# as5047_breakout.net
KiCad netlist of a schematic drawn in EAGLE
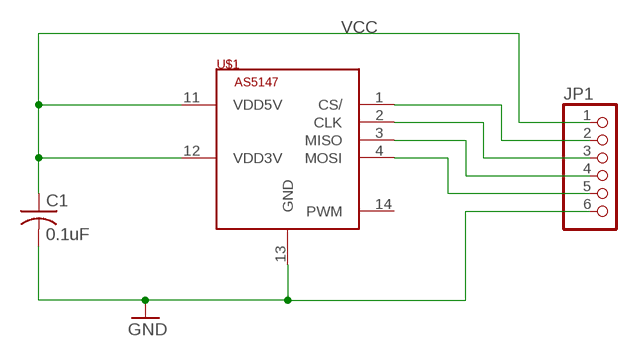
[diagram p0: schematic, sheet 1]

(export (version "E")
  (design (tool "Eeschema 10.0.6"))
  (components
    (comp (ref "C1")
      (value "0.1uF")
      (footprint "eagle-import:C0603")
      (libsource (lib "eagle-import") (part "C-USC0603"))
    )
    (comp (ref "JP1")
      (value "PINHD-1X6")
      (footprint "eagle-import:1X06")
      (libsource (lib "eagle-import") (part "PINHD-1X6"))
    )
    (comp (ref "U$1")
      (value "AS5147")
      (footprint "eagle-import:TSSOP14")
      (fields (field (name "MFG") "AMS") (field (name "MPN") "AS5047D-ATSM"))
      (libsource (lib "eagle-import") (part "AS5147"))
    )
  )
  (nets
    (net (code "1") (name "/VCC") (class "Default")
      (node (ref "C1") (pin "1") (pinfunction "1_1") (pintype "passive"))
      (node (ref "JP1") (pin "1") (pinfunction "1_1") (pintype "passive"))
      (node (ref "U$1") (pin "11") (pinfunction "VDD5V_11") (pintype "bidirectional"))
      (node (ref "U$1") (pin "12") (pinfunction "VDD3V_12") (pintype "bidirectional"))
    )
    (net (code "2") (name "GND") (class "Default")
      (node (ref "C1") (pin "2") (pinfunction "2_2") (pintype "passive"))
      (node (ref "JP1") (pin "6") (pinfunction "6_6") (pintype "passive"))
      (node (ref "U$1") (pin "13") (pinfunction "GND_13") (pintype "bidirectional"))
    )
    (net (code "3") (name "Net-(U$1-CLK)") (class "Default")
      (node (ref "JP1") (pin "3") (pinfunction "3_3") (pintype "passive"))
      (node (ref "U$1") (pin "2") (pinfunction "CLK_2") (pintype "bidirectional"))
    )
    (net (code "4") (name "Net-(U$1-CS{slash})") (class "Default")
      (node (ref "JP1") (pin "2") (pinfunction "2_2") (pintype "passive"))
      (node (ref "U$1") (pin "1") (pinfunction "CS/_1") (pintype "bidirectional"))
    )
    (net (code "5") (name "Net-(U$1-MISO)") (class "Default")
      (node (ref "JP1") (pin "4") (pinfunction "4_4") (pintype "passive"))
      (node (ref "U$1") (pin "3") (pinfunction "MISO_3") (pintype "bidirectional"))
    )
    (net (code "6") (name "Net-(U$1-MOSI)") (class "Default")
      (node (ref "JP1") (pin "5") (pinfunction "5_5") (pintype "passive"))
      (node (ref "U$1") (pin "4") (pinfunction "MOSI_4") (pintype "bidirectional"))
    )
    (net (code "7") (name "unconnected-(U$1-PWM-Pad14)") (class "Default")
      (node (ref "U$1") (pin "14") (pinfunction "PWM_14") (pintype "bidirectional"))
    )
  )
)
